# S03.net
KiCad netlist of a schematic drawn in Altium Designer
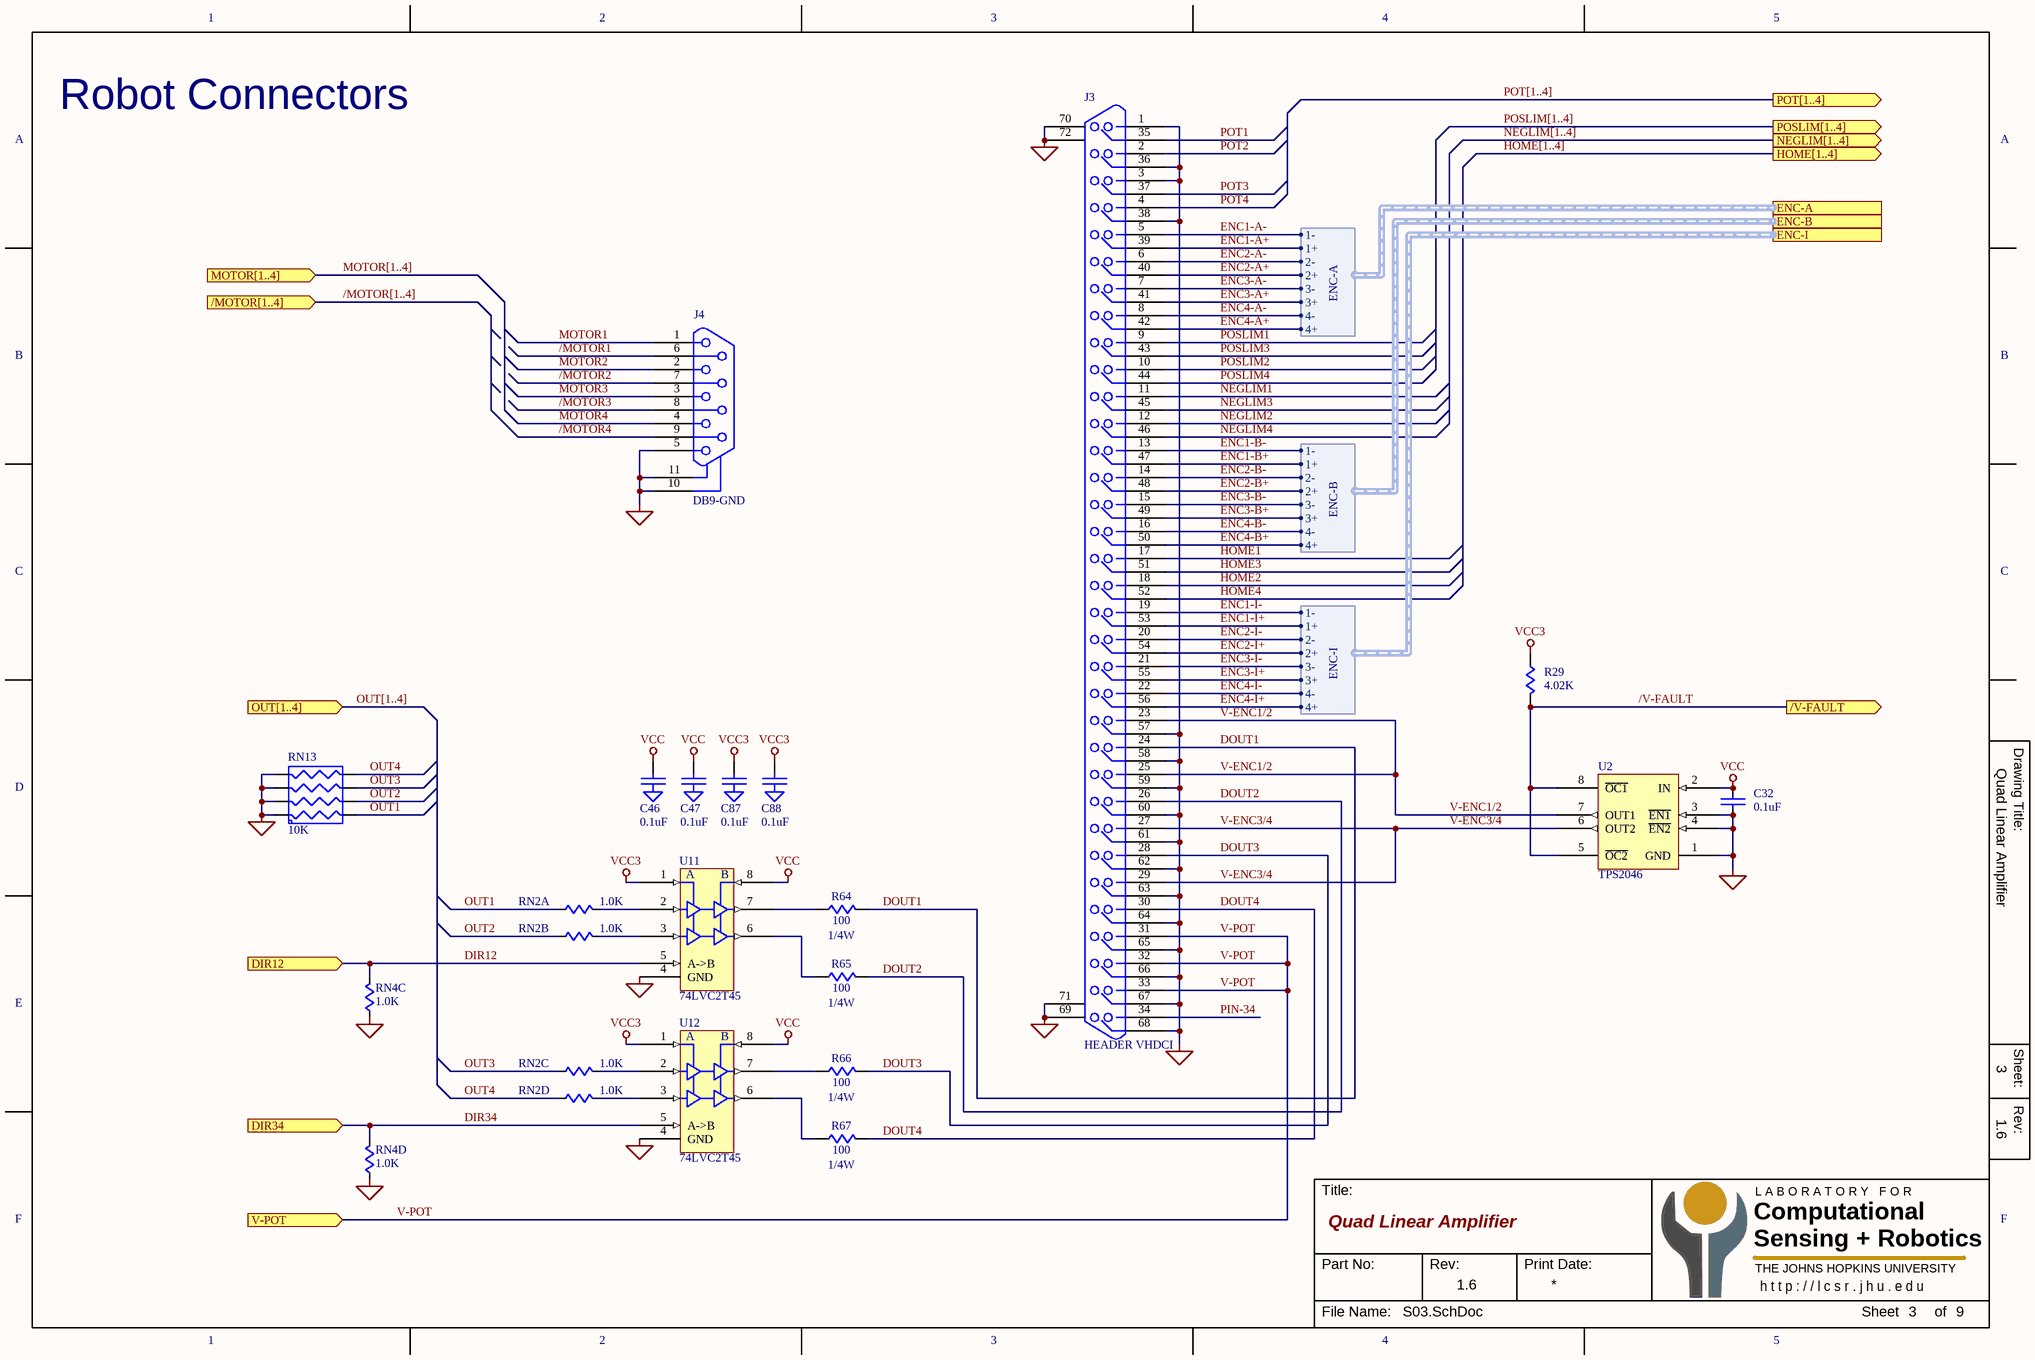
[diagram p0: S03.SchDoc]

(export (version "E")
  (design (tool "Eeschema 10.0.6"))
  (components
    (comp (ref "C32") (value "0.1uF") (footprint "C0603") (libsource (lib "QLA") (part "CAP-MINI")))
    (comp (ref "C46") (value "0.1uF") (footprint "C0603") (libsource (lib "QLA") (part "CAP-GND")))
    (comp (ref "C47") (value "0.1uF") (footprint "C0603") (libsource (lib "QLA") (part "CAP-GND")))
    (comp (ref "C87") (value "0.1uF") (footprint "C0603") (libsource (lib "QLA") (part "CAP-GND")))
    (comp (ref "C88") (value "0.1uF") (footprint "C0603") (libsource (lib "QLA") (part "CAP-GND")))
    (comp (ref "J3")
      (value "HEADER VHDCI")
      (footprint "CONN-VHDCI")
      (description "Molex Part #71430-0008")
      (libsource (lib "QLA") (part "HEADER VHDCI"))
    )
    (comp (ref "J4") (value "DB9-GND") (footprint "DB9F/RA-545-HDP") (libsource (lib "QLA") (part "DB9-GND")))
    (comp (ref "R29") (value "4.02K") (footprint "R0603") (libsource (lib "QLA") (part "R")))
    (comp (ref "R64")
      (value "100")
      (footprint "R1206")
      (fields (field (name "ALTIUM_UNNAMED_1") "1/4W"))
      (libsource (lib "QLA") (part "R"))
    )
    (comp (ref "R65")
      (value "100")
      (footprint "R1206")
      (fields (field (name "ALTIUM_UNNAMED_1") "1/4W"))
      (libsource (lib "QLA") (part "R"))
    )
    (comp (ref "R66")
      (value "100")
      (footprint "R1206")
      (fields (field (name "ALTIUM_UNNAMED_1") "1/4W"))
      (libsource (lib "QLA") (part "R"))
    )
    (comp (ref "R67")
      (value "100")
      (footprint "R1206")
      (fields (field (name "ALTIUM_UNNAMED_1") "1/4W"))
      (libsource (lib "QLA") (part "R"))
    )
    (comp (ref "RN2") (value "1.0K") (footprint "RN-742C083") (libsource (lib "QLA") (part "RN-DISC-SM-4X")))
    (comp (ref "RN4") (value "1.0K") (footprint "RN-742C083") (libsource (lib "QLA") (part "RN-DISC-SM-4X")))
    (comp (ref "RN13") (value "10K") (footprint "RN-742C083") (libsource (lib "QLA") (part "RN-DISC-SM-4")))
    (comp (ref "U2") (value "TPS2046") (footprint "SO-8") (libsource (lib "QLA") (part "TPS2046")))
    (comp (ref "U11") (value "74LVC2T45") (footprint "US8-8") (libsource (lib "QLA") (part "74LVC2T45")))
    (comp (ref "U12") (value "74LVC2T45") (footprint "US8-8") (libsource (lib "QLA") (part "74LVC2T45")))
  )
  (nets
    (net (code "8") (name "/DIR12") (class "Default")
      (node (ref "RN4") (pin "6") (pinfunction "6_6") (pintype "passive"))
      (node (ref "U11") (pin "5") (pinfunction "A->B_5") (pintype "input"))
    )
    (net (code "9") (name "/DIR34") (class "Default")
      (node (ref "RN4") (pin "5") (pinfunction "5_5") (pintype "passive"))
      (node (ref "U12") (pin "5") (pinfunction "A->B_5") (pintype "input"))
    )
    (net (code "10") (name "/DOUT1") (class "Default")
      (node (ref "J3") (pin "24") (pinfunction "24_24") (pintype "passive"))
      (node (ref "R64") (pin "2") (pinfunction "2_2") (pintype "passive"))
    )
    (net (code "11") (name "/DOUT2") (class "Default")
      (node (ref "J3") (pin "26") (pinfunction "26_26") (pintype "passive"))
      (node (ref "R65") (pin "2") (pinfunction "2_2") (pintype "passive"))
    )
    (net (code "12") (name "/DOUT3") (class "Default")
      (node (ref "J3") (pin "28") (pinfunction "28_28") (pintype "passive"))
      (node (ref "R66") (pin "2") (pinfunction "2_2") (pintype "passive"))
    )
    (net (code "13") (name "/DOUT4") (class "Default")
      (node (ref "J3") (pin "30") (pinfunction "30_30") (pintype "passive"))
      (node (ref "R67") (pin "2") (pinfunction "2_2") (pintype "passive"))
    )
    (net (code "14") (name "/ENC1-A+") (class "Default")
      (node (ref "J3") (pin "39") (pinfunction "39_39") (pintype "passive"))
    )
    (net (code "15") (name "/ENC1-A-") (class "Default")
      (node (ref "J3") (pin "5") (pinfunction "5_5") (pintype "passive"))
    )
    (net (code "16") (name "/ENC1-B+") (class "Default")
      (node (ref "J3") (pin "47") (pinfunction "47_47") (pintype "passive"))
    )
    (net (code "17") (name "/ENC1-B-") (class "Default")
      (node (ref "J3") (pin "13") (pinfunction "13_13") (pintype "passive"))
    )
    (net (code "18") (name "/ENC1-I+") (class "Default")
      (node (ref "J3") (pin "53") (pinfunction "53_53") (pintype "passive"))
    )
    (net (code "19") (name "/ENC1-I-") (class "Default")
      (node (ref "J3") (pin "19") (pinfunction "19_19") (pintype "passive"))
    )
    (net (code "20") (name "/ENC2-A+") (class "Default")
      (node (ref "J3") (pin "40") (pinfunction "40_40") (pintype "passive"))
    )
    (net (code "21") (name "/ENC2-A-") (class "Default")
      (node (ref "J3") (pin "6") (pinfunction "6_6") (pintype "passive"))
    )
    (net (code "22") (name "/ENC2-B+") (class "Default")
      (node (ref "J3") (pin "48") (pinfunction "48_48") (pintype "passive"))
    )
    (net (code "23") (name "/ENC2-B-") (class "Default")
      (node (ref "J3") (pin "14") (pinfunction "14_14") (pintype "passive"))
    )
    (net (code "24") (name "/ENC2-I+") (class "Default")
      (node (ref "J3") (pin "54") (pinfunction "54_54") (pintype "passive"))
    )
    (net (code "25") (name "/ENC2-I-") (class "Default")
      (node (ref "J3") (pin "20") (pinfunction "20_20") (pintype "passive"))
    )
    (net (code "26") (name "/ENC3-A+") (class "Default")
      (node (ref "J3") (pin "41") (pinfunction "41_41") (pintype "passive"))
    )
    (net (code "27") (name "/ENC3-A-") (class "Default")
      (node (ref "J3") (pin "7") (pinfunction "7_7") (pintype "passive"))
    )
    (net (code "28") (name "/ENC3-B+") (class "Default")
      (node (ref "J3") (pin "49") (pinfunction "49_49") (pintype "passive"))
    )
    (net (code "29") (name "/ENC3-B-") (class "Default")
      (node (ref "J3") (pin "15") (pinfunction "15_15") (pintype "passive"))
    )
    (net (code "30") (name "/ENC3-I+") (class "Default")
      (node (ref "J3") (pin "55") (pinfunction "55_55") (pintype "passive"))
    )
    (net (code "31") (name "/ENC3-I-") (class "Default")
      (node (ref "J3") (pin "21") (pinfunction "21_21") (pintype "passive"))
    )
    (net (code "32") (name "/ENC4-A+") (class "Default")
      (node (ref "J3") (pin "42") (pinfunction "42_42") (pintype "passive"))
    )
    (net (code "33") (name "/ENC4-A-") (class "Default")
      (node (ref "J3") (pin "8") (pinfunction "8_8") (pintype "passive"))
    )
    (net (code "34") (name "/ENC4-B+") (class "Default")
      (node (ref "J3") (pin "50") (pinfunction "50_50") (pintype "passive"))
    )
    (net (code "35") (name "/ENC4-B-") (class "Default")
      (node (ref "J3") (pin "16") (pinfunction "16_16") (pintype "passive"))
    )
    (net (code "36") (name "/ENC4-I+") (class "Default")
      (node (ref "J3") (pin "56") (pinfunction "56_56") (pintype "passive"))
    )
    (net (code "37") (name "/ENC4-I-") (class "Default")
      (node (ref "J3") (pin "22") (pinfunction "22_22") (pintype "passive"))
    )
    (net (code "38") (name "/HOME1") (class "Default")
      (node (ref "J3") (pin "17") (pinfunction "17_17") (pintype "passive"))
    )
    (net (code "39") (name "/HOME2") (class "Default")
      (node (ref "J3") (pin "18") (pinfunction "18_18") (pintype "passive"))
    )
    (net (code "40") (name "/HOME3") (class "Default")
      (node (ref "J3") (pin "51") (pinfunction "51_51") (pintype "passive"))
    )
    (net (code "41") (name "/HOME4") (class "Default")
      (node (ref "J3") (pin "52") (pinfunction "52_52") (pintype "passive"))
    )
    (net (code "43") (name "/MOTOR1") (class "Default") (node (ref "J4") (pin "1") (pintype "passive")))
    (net (code "44") (name "/MOTOR2") (class "Default") (node (ref "J4") (pin "2") (pintype "passive")))
    (net (code "45") (name "/MOTOR3") (class "Default") (node (ref "J4") (pin "3") (pintype "passive")))
    (net (code "46") (name "/MOTOR4") (class "Default") (node (ref "J4") (pin "4") (pintype "passive")))
    (net (code "48") (name "/NEGLIM1") (class "Default")
      (node (ref "J3") (pin "11") (pinfunction "11_11") (pintype "passive"))
    )
    (net (code "49") (name "/NEGLIM2") (class "Default")
      (node (ref "J3") (pin "12") (pinfunction "12_12") (pintype "passive"))
    )
    (net (code "50") (name "/NEGLIM3") (class "Default")
      (node (ref "J3") (pin "45") (pinfunction "45_45") (pintype "passive"))
    )
    (net (code "51") (name "/NEGLIM4") (class "Default")
      (node (ref "J3") (pin "46") (pinfunction "46_46") (pintype "passive"))
    )
    (net (code "53") (name "/OUT1") (class "Default")
      (node (ref "RN13") (pin "8") (pinfunction "R1.2_8") (pintype "passive"))
      (node (ref "RN2") (pin "1") (pinfunction "1_1") (pintype "passive"))
    )
    (net (code "54") (name "/OUT2") (class "Default")
      (node (ref "RN13") (pin "7") (pinfunction "R2.2_7") (pintype "passive"))
      (node (ref "RN2") (pin "2") (pinfunction "2_2") (pintype "passive"))
    )
    (net (code "55") (name "/OUT3") (class "Default")
      (node (ref "RN13") (pin "6") (pinfunction "R3.2_6") (pintype "passive"))
      (node (ref "RN2") (pin "3") (pinfunction "3_3") (pintype "passive"))
    )
    (net (code "56") (name "/OUT4") (class "Default")
      (node (ref "RN13") (pin "5") (pinfunction "R4.2_5") (pintype "passive"))
      (node (ref "RN2") (pin "4") (pinfunction "4_4") (pintype "passive"))
    )
    (net (code "58") (name "/PIN-34") (class "Default")
      (node (ref "J3") (pin "34") (pinfunction "34_34") (pintype "passive"))
    )
    (net (code "59") (name "/POSLIM1") (class "Default")
      (node (ref "J3") (pin "9") (pinfunction "9_9") (pintype "passive"))
    )
    (net (code "60") (name "/POSLIM2") (class "Default")
      (node (ref "J3") (pin "10") (pinfunction "10_10") (pintype "passive"))
    )
    (net (code "61") (name "/POSLIM3") (class "Default")
      (node (ref "J3") (pin "43") (pinfunction "43_43") (pintype "passive"))
    )
    (net (code "62") (name "/POSLIM4") (class "Default")
      (node (ref "J3") (pin "44") (pinfunction "44_44") (pintype "passive"))
    )
    (net (code "64") (name "/POT1") (class "Default")
      (node (ref "J3") (pin "35") (pinfunction "35_35") (pintype "passive"))
    )
    (net (code "65") (name "/POT2") (class "Default")
      (node (ref "J3") (pin "2") (pinfunction "2_2") (pintype "passive"))
    )
    (net (code "66") (name "/POT3") (class "Default")
      (node (ref "J3") (pin "37") (pinfunction "37_37") (pintype "passive"))
    )
    (net (code "67") (name "/POT4") (class "Default")
      (node (ref "J3") (pin "4") (pinfunction "4_4") (pintype "passive"))
    )
    (net (code "69") (name "/V-ENC1{slash}2") (class "Default")
      (node (ref "J3") (pin "23") (pinfunction "23_23") (pintype "passive"))
      (node (ref "J3") (pin "25") (pinfunction "25_25") (pintype "passive"))
      (node (ref "U2") (pin "7") (pinfunction "OUT1_7") (pintype "output"))
    )
    (net (code "70") (name "/V-ENC3{slash}4") (class "Default")
      (node (ref "J3") (pin "27") (pinfunction "27_27") (pintype "passive"))
      (node (ref "J3") (pin "29") (pinfunction "29_29") (pintype "passive"))
      (node (ref "U2") (pin "6") (pinfunction "OUT2_6") (pintype "output"))
    )
    (net (code "71") (name "/V-POT") (class "Default")
      (node (ref "J3") (pin "31") (pinfunction "31_31") (pintype "passive"))
      (node (ref "J3") (pin "32") (pinfunction "32_32") (pintype "passive"))
      (node (ref "J3") (pin "33") (pinfunction "33_33") (pintype "passive"))
    )
    (net (code "75") (name "/{slash}MOTOR1") (class "Default")
      (node (ref "J4") (pin "6") (pintype "passive"))
    )
    (net (code "76") (name "/{slash}MOTOR2") (class "Default")
      (node (ref "J4") (pin "7") (pintype "passive"))
    )
    (net (code "77") (name "/{slash}MOTOR3") (class "Default")
      (node (ref "J4") (pin "8") (pintype "passive"))
    )
    (net (code "78") (name "/{slash}MOTOR4") (class "Default")
      (node (ref "J4") (pin "9") (pintype "passive"))
    )
    (net (code "80") (name "/{slash}V-FAULT") (class "Default")
      (node (ref "R29") (pin "2") (pinfunction "2_2") (pintype "passive"))
      (node (ref "U2") (pin "5") (pinfunction "OC2_5") (pintype "open_collector"))
      (node (ref "U2") (pin "8") (pinfunction "OC1_8") (pintype "open_collector"))
    )
    (net (code "81") (name "GND") (class "Default")
      (node (ref "C32") (pin "2") (pintype "passive"))
      (node (ref "C46") (pin "2") (pinfunction "GND_2") (pintype "power_in"))
      (node (ref "C47") (pin "2") (pinfunction "GND_2") (pintype "power_in"))
      (node (ref "C87") (pin "2") (pinfunction "GND_2") (pintype "power_in"))
      (node (ref "C88") (pin "2") (pinfunction "GND_2") (pintype "power_in"))
      (node (ref "J3") (pin "1") (pinfunction "1_1") (pintype "passive"))
      (node (ref "J3") (pin "3") (pinfunction "3_3") (pintype "passive"))
      (node (ref "J3") (pin "36") (pinfunction "36_36") (pintype "passive"))
      (node (ref "J3") (pin "38") (pinfunction "38_38") (pintype "passive"))
      (node (ref "J3") (pin "57") (pinfunction "57_57") (pintype "passive"))
      (node (ref "J3") (pin "58") (pinfunction "58_58") (pintype "passive"))
      (node (ref "J3") (pin "59") (pinfunction "59_59") (pintype "passive"))
      (node (ref "J3") (pin "60") (pinfunction "60_60") (pintype "passive"))
      (node (ref "J3") (pin "61") (pinfunction "61_61") (pintype "passive"))
      (node (ref "J3") (pin "62") (pinfunction "62_62") (pintype "passive"))
      (node (ref "J3") (pin "63") (pinfunction "63_63") (pintype "passive"))
      (node (ref "J3") (pin "64") (pinfunction "64_64") (pintype "passive"))
      (node (ref "J3") (pin "65") (pinfunction "65_65") (pintype "passive"))
      (node (ref "J3") (pin "66") (pinfunction "66_66") (pintype "passive"))
      (node (ref "J3") (pin "67") (pinfunction "67_67") (pintype "passive"))
      (node (ref "J3") (pin "68") (pinfunction "68_68") (pintype "passive"))
      (node (ref "J3") (pin "69") (pinfunction "69_69") (pintype "passive"))
      (node (ref "J3") (pin "70") (pinfunction "70_70") (pintype "passive"))
      (node (ref "J3") (pin "71") (pinfunction "71_71") (pintype "passive"))
      (node (ref "J3") (pin "72") (pinfunction "72_72") (pintype "passive"))
      (node (ref "J4") (pin "10") (pinfunction "GND_10") (pintype "power_in"))
      (node (ref "J4") (pin "11") (pinfunction "GND_11") (pintype "power_in"))
      (node (ref "J4") (pin "5") (pintype "passive"))
      (node (ref "RN13") (pin "1") (pinfunction "R1_1") (pintype "passive"))
      (node (ref "RN13") (pin "2") (pinfunction "R2.1_2") (pintype "passive"))
      (node (ref "RN13") (pin "3") (pinfunction "R3.1_3") (pintype "passive"))
      (node (ref "RN13") (pin "4") (pinfunction "R4.1_4") (pintype "passive"))
      (node (ref "RN4") (pin "3") (pinfunction "3_3") (pintype "passive"))
      (node (ref "RN4") (pin "4") (pinfunction "4_4") (pintype "passive"))
      (node (ref "U11") (pin "4") (pinfunction "GND_4") (pintype "power_in"))
      (node (ref "U12") (pin "4") (pinfunction "GND_4") (pintype "power_in"))
      (node (ref "U2") (pin "1") (pinfunction "GND_1") (pintype "power_in"))
      (node (ref "U2") (pin "3") (pinfunction "EN1_3") (pintype "input"))
      (node (ref "U2") (pin "4") (pinfunction "EN2_4") (pintype "input"))
    )
    (net (code "82") (name "Net-(R64-Pad1)") (class "Default")
      (node (ref "R64") (pin "1") (pinfunction "1_1") (pintype "passive"))
      (node (ref "U11") (pin "7") (pinfunction "B_7") (pintype "output"))
    )
    (net (code "83") (name "Net-(R65-Pad1)") (class "Default")
      (node (ref "R65") (pin "1") (pinfunction "1_1") (pintype "passive"))
      (node (ref "U11") (pin "6") (pinfunction "B_6") (pintype "output"))
    )
    (net (code "84") (name "Net-(R66-Pad1)") (class "Default")
      (node (ref "R66") (pin "1") (pinfunction "1_1") (pintype "passive"))
      (node (ref "U12") (pin "7") (pinfunction "B_7") (pintype "output"))
    )
    (net (code "85") (name "Net-(R67-Pad1)") (class "Default")
      (node (ref "R67") (pin "1") (pinfunction "1_1") (pintype "passive"))
      (node (ref "U12") (pin "6") (pinfunction "B_6") (pintype "output"))
    )
    (net (code "86") (name "Net-(RN2-Pad5)") (class "Default")
      (node (ref "RN2") (pin "5") (pinfunction "5_5") (pintype "passive"))
      (node (ref "U12") (pin "3") (pinfunction "A_3") (pintype "input"))
    )
    (net (code "87") (name "Net-(RN2-Pad6)") (class "Default")
      (node (ref "RN2") (pin "6") (pinfunction "6_6") (pintype "passive"))
      (node (ref "U12") (pin "2") (pinfunction "A_2") (pintype "input"))
    )
    (net (code "88") (name "Net-(RN2-Pad7)") (class "Default")
      (node (ref "RN2") (pin "7") (pinfunction "7_7") (pintype "passive"))
      (node (ref "U11") (pin "3") (pinfunction "A_3") (pintype "input"))
    )
    (net (code "89") (name "Net-(RN2-Pad8)") (class "Default")
      (node (ref "RN2") (pin "8") (pinfunction "8_8") (pintype "passive"))
      (node (ref "U11") (pin "2") (pinfunction "A_2") (pintype "input"))
    )
    (net (code "90") (name "VCC") (class "Default")
      (node (ref "C32") (pin "1") (pintype "passive"))
      (node (ref "C46") (pin "1") (pintype "passive"))
      (node (ref "C47") (pin "1") (pintype "passive"))
      (node (ref "U11") (pin "8") (pinfunction "VCCB_8") (pintype "input"))
      (node (ref "U12") (pin "8") (pinfunction "VCCB_8") (pintype "input"))
      (node (ref "U2") (pin "2") (pinfunction "IN_2") (pintype "input"))
    )
    (net (code "91") (name "VCC3") (class "Default")
      (node (ref "C87") (pin "1") (pintype "passive"))
      (node (ref "C88") (pin "1") (pintype "passive"))
      (node (ref "R29") (pin "1") (pinfunction "1_1") (pintype "passive"))
      (node (ref "U11") (pin "1") (pinfunction "VCCA_1") (pintype "input"))
      (node (ref "U12") (pin "1") (pinfunction "VCCA_1") (pintype "input"))
    )
  )
)
